# Switch.net
KiCad netlist of a schematic drawn in Altium Designer
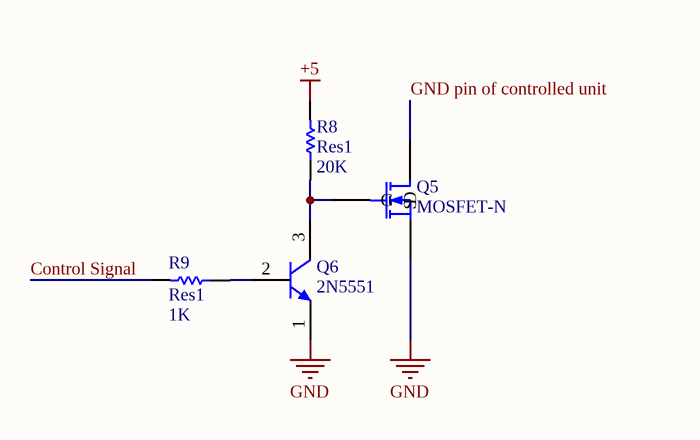
[diagram p0: Switch.SchDoc]

(export (version "E")
  (design (tool "Eeschema 10.0.6"))
  (components
    (comp (ref "Q5")
      (value "MOSFET-N")
      (footprint "TO-220-AB")
      (description "N-Channel MOSFET")
      (fields (field (name "PUBLISHER") "Altium Limited"))
      (libsource (lib "Miscellaneous Devices") (part "MOSFET-N"))
    )
    (comp (ref "Q6")
      (value "2N5551")
      (footprint "TO-92A")
      (description "NPN General Purpose Amplifier")
      (fields (field (name "PUBLISHER") "Altium Limited"))
      (libsource (lib "Miscellaneous Devices") (part "2N3904"))
    )
    (comp (ref "R8")
      (value "Res1")
      (footprint "AXIAL-0.3")
      (description "Resistor")
      (fields (field (name "ALTIUM_VALUE") "20K") (field (name "PUBLISHER") "Altium Limited"))
      (libsource (lib "Miscellaneous Devices") (part "Res1"))
    )
    (comp (ref "R9")
      (value "Res1")
      (footprint "AXIAL-0.3")
      (description "Resistor")
      (fields (field (name "ALTIUM_VALUE") "1K") (field (name "PUBLISHER") "Altium Limited"))
      (libsource (lib "Miscellaneous Devices") (part "Res1"))
    )
  )
  (nets
    (net (code "1") (name "+5") (class "Default")
      (node (ref "R8") (pin "2") (pinfunction "2_2") (pintype "passive"))
    )
    (net (code "2") (name "/Control Signal") (class "Default")
      (node (ref "R9") (pin "2") (pinfunction "2_2") (pintype "passive"))
    )
    (net (code "3") (name "/GND pin of controlled unit") (class "Default")
      (node (ref "Q5") (pin "2") (pinfunction "D_2") (pintype "passive"))
    )
    (net (code "4") (name "GND") (class "Default")
      (node (ref "Q5") (pin "3") (pinfunction "S_3") (pintype "passive"))
      (node (ref "Q6") (pin "1") (pinfunction "E_1") (pintype "passive"))
    )
    (net (code "5") (name "Net-(Q5-G)") (class "Default")
      (node (ref "Q5") (pin "1") (pinfunction "G_1") (pintype "passive"))
      (node (ref "Q6") (pin "3") (pinfunction "C_3") (pintype "passive"))
      (node (ref "R8") (pin "1") (pinfunction "1_1") (pintype "passive"))
    )
    (net (code "6") (name "Net-(Q6-B)") (class "Default")
      (node (ref "Q6") (pin "2") (pinfunction "B_2") (pintype "passive"))
      (node (ref "R9") (pin "1") (pinfunction "1_1") (pintype "passive"))
    )
  )
)
